# MAGI_sBatteryPowerMega.net
KiCad netlist of a schematic drawn in Altium Designer
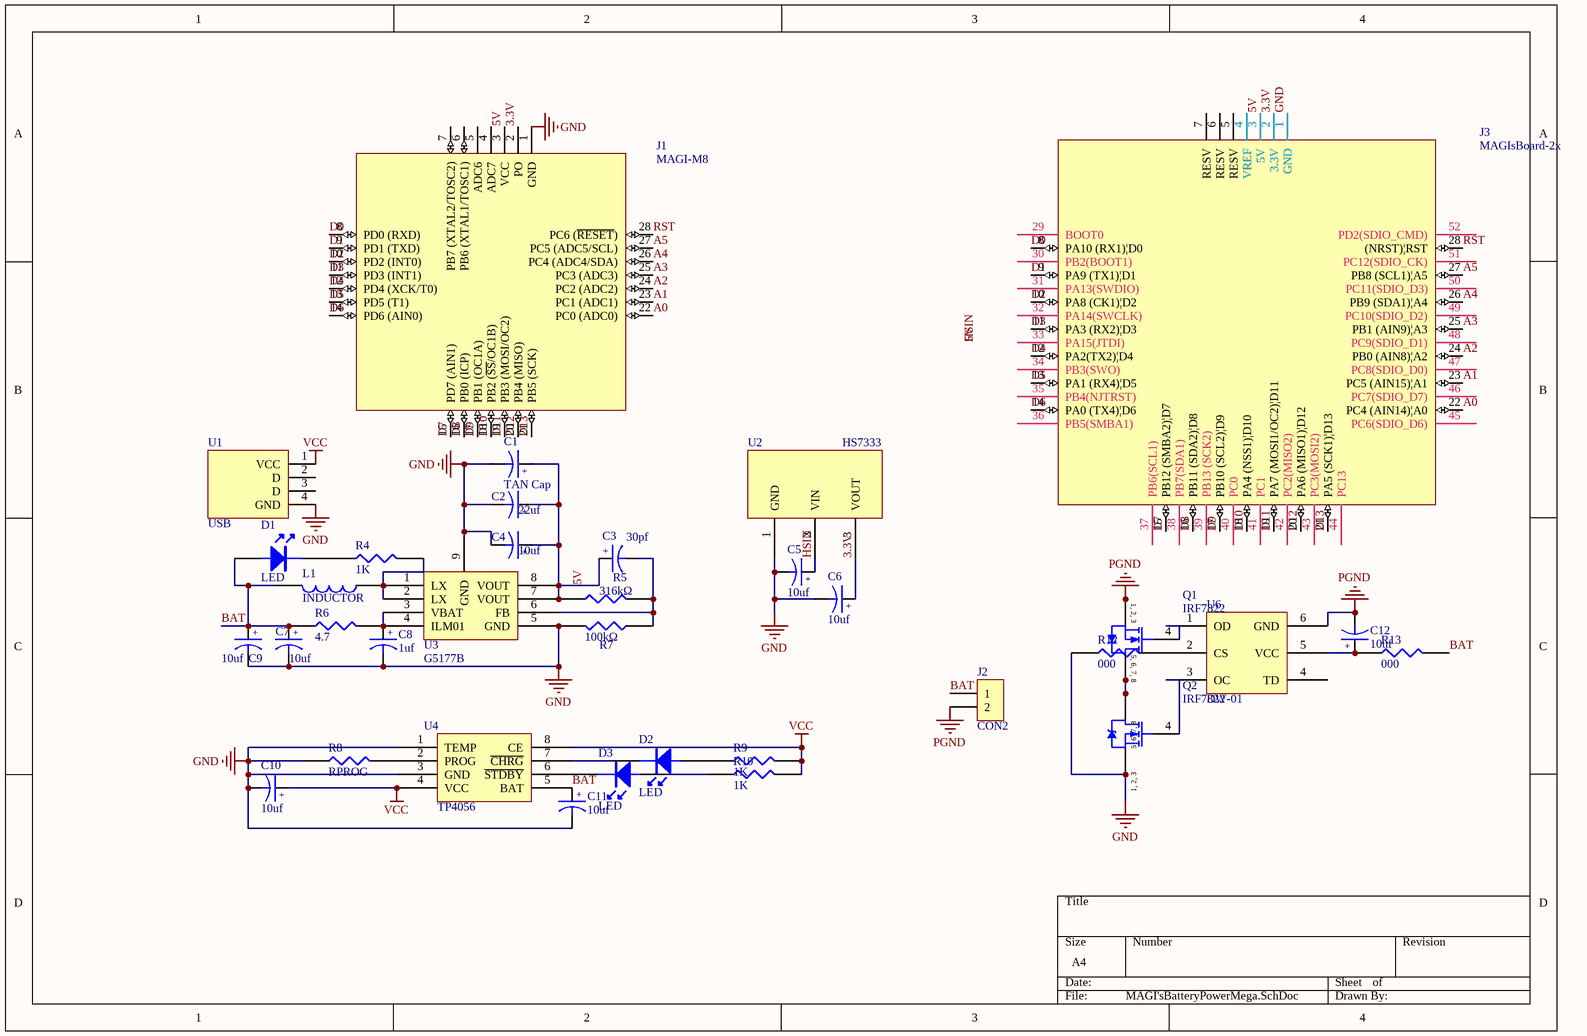
[diagram p0: MAGI'sBatteryPowerMega.SchDoc]

(export (version "E")
  (design (tool "Eeschema 10.0.6"))
  (components
    (comp (ref "C1")
      (value "TAN Cap")
      (footprint "TAN-D-7343")
      (description "Capacitor")
      (libsource (lib "电容器") (part "CAPACITOR POL"))
    )
    (comp (ref "C2")
      (value "22uf")
      (footprint "14-1210")
      (description "Capacitor")
      (libsource (lib "电容器") (part "CAPACITOR POL"))
    )
    (comp (ref "C3")
      (value "30pf")
      (footprint "6-0805_N")
      (description "Capacitor")
      (libsource (lib "电容器") (part "CAPACITOR POL"))
    )
    (comp (ref "C4")
      (value "10uf")
      (footprint "6-0805_N")
      (description "Capacitor")
      (libsource (lib "电容器") (part "CAPACITOR POL"))
    )
    (comp (ref "C5")
      (value "10uf")
      (footprint "6-0805_N")
      (description "Capacitor")
      (libsource (lib "电容器") (part "CAPACITOR POL"))
    )
    (comp (ref "C6")
      (value "10uf")
      (footprint "6-0805_N")
      (description "Capacitor")
      (libsource (lib "电容器") (part "CAPACITOR POL"))
    )
    (comp (ref "C7")
      (value "10uf")
      (footprint "6-0805_N")
      (description "Capacitor")
      (libsource (lib "电容器") (part "CAPACITOR POL"))
    )
    (comp (ref "C8")
      (value "1uf")
      (footprint "6-0805_N")
      (description "Capacitor")
      (libsource (lib "电容器") (part "CAPACITOR POL"))
    )
    (comp (ref "C9")
      (value "10uf")
      (footprint "6-0805_N")
      (description "Capacitor")
      (libsource (lib "电容器") (part "CAPACITOR POL"))
    )
    (comp (ref "C10")
      (value "10uf")
      (footprint "6-0805_N")
      (description "Capacitor")
      (libsource (lib "电容器") (part "CAPACITOR POL"))
    )
    (comp (ref "C11")
      (value "10uf")
      (footprint "6-0805_N")
      (description "Capacitor")
      (libsource (lib "电容器") (part "CAPACITOR POL"))
    )
    (comp (ref "C12")
      (value "10uf")
      (footprint "6-0805_N")
      (description "Capacitor")
      (libsource (lib "电容器") (part "CAPACITOR POL"))
    )
    (comp (ref "D1") (value "LED") (footprint "6-0805_N") (libsource (lib "二极管") (part "LED")))
    (comp (ref "D2") (value "LED") (footprint "6-0805_N") (libsource (lib "二极管") (part "LED")))
    (comp (ref "D3") (value "LED") (footprint "6-0805_N") (libsource (lib "二极管") (part "LED")))
    (comp (ref "J1") (value "MAGI-M8") (footprint "MAGI-M8") (libsource (lib "MAGI-M8") (part "MAGI-M8")))
    (comp (ref "J2")
      (value "CON2")
      (footprint "18650")
      (description "Connector")
      (libsource (lib "CON系列") (part "CON2"))
    )
    (comp (ref "J3")
      (value "MAGIsBoard-2x")
      (footprint "MAGIsBoard-2x")
      (libsource (lib "MAGIsBoard") (part "MAGIsBoard-2x"))
    )
    (comp (ref "L1") (value "INDUCTOR") (footprint "7*7") (libsource (lib "汇总") (part "INDUCTOR")))
    (comp (ref "Q1")
      (value "IRF7822")
      (footprint "SO-8_N")
      (description "HEXFET Power MOSFET")
      (fields (field (name "PUBLISHER") "Altium Limited"))
      (libsource (lib "IR Discrete MOSFET - Power") (part "IRF7822"))
    )
    (comp (ref "Q2")
      (value "IRF7822")
      (footprint "SO-8_N")
      (description "HEXFET Power MOSFET")
      (fields (field (name "PUBLISHER") "Altium Limited"))
      (libsource (lib "IR Discrete MOSFET - Power") (part "IRF7822"))
    )
    (comp (ref "R4") (value "1K") (footprint "6-0805_N") (libsource (lib "电阻器") (part "RES1")))
    (comp (ref "R5") (value "316kΩ") (footprint "6-0805_N") (libsource (lib "电阻器") (part "RES1")))
    (comp (ref "R6") (value "4.7") (footprint "6-0805_N") (libsource (lib "电阻器") (part "RES1")))
    (comp (ref "R7") (value "100kΩ") (footprint "6-0805_N") (libsource (lib "电阻器") (part "RES1")))
    (comp (ref "R8") (value "RPROG") (footprint "6-0805_N") (libsource (lib "电阻器") (part "RES1")))
    (comp (ref "R9") (value "1K") (footprint "6-0805_N") (libsource (lib "电阻器") (part "RES1")))
    (comp (ref "R10") (value "1K") (footprint "6-0805_N") (libsource (lib "电阻器") (part "RES1")))
    (comp (ref "R12") (value "000") (footprint "6-0805_n") (libsource (lib "电阻器") (part "RES1")))
    (comp (ref "R13") (value "000") (footprint "6-0805_n") (libsource (lib "电阻器") (part "RES1")))
    (comp (ref "U1") (value "USB") (footprint "MicroUSB") (libsource (lib "USB接口") (part "USB")))
    (comp (ref "U2") (value "HS7333") (footprint "HS7333") (libsource (lib "PMIC") (part "HS7333")))
    (comp (ref "U3") (value "G5177B") (footprint "G5177B") (libsource (lib "PMIC") (part "G5177B")))
    (comp (ref "U4") (value "TP4056") (footprint "TP4056") (libsource (lib "PMIC") (part "TP4056")))
    (comp (ref "U6") (value "DW-01") (footprint "TPS2513") (libsource (lib "PMIC") (part "TPS2513")))
  )
  (nets
    (net (code "1") (name "/3.3V") (class "Default")
      (node (ref "C6") (pin "1") (pinfunction "1_1") (pintype "passive"))
      (node (ref "J1") (pin "2") (pinfunction "PO_2") (pintype "power_in"))
      (node (ref "J3") (pin "2") (pinfunction "3.3V_2") (pintype "power_in"))
      (node (ref "U2") (pin "3") (pinfunction "VOUT_3") (pintype "passive"))
    )
    (net (code "2") (name "/5V") (class "Default")
      (node (ref "C1") (pin "1") (pinfunction "1_1") (pintype "passive"))
      (node (ref "C2") (pin "1") (pinfunction "1_1") (pintype "passive"))
      (node (ref "C3") (pin "1") (pinfunction "1_1") (pintype "passive"))
      (node (ref "C4") (pin "1") (pinfunction "1_1") (pintype "passive"))
      (node (ref "C5") (pin "1") (pinfunction "1_1") (pintype "passive"))
      (node (ref "J1") (pin "3") (pinfunction "VCC_3") (pintype "power_in"))
      (node (ref "J3") (pin "3") (pinfunction "5V_3") (pintype "power_in"))
      (node (ref "R5") (pin "1") (pinfunction "1_1") (pintype "passive"))
      (node (ref "U2") (pin "2") (pinfunction "VIN_2") (pintype "passive"))
      (node (ref "U3") (pin "7") (pinfunction "VOUT_7") (pintype "passive"))
      (node (ref "U3") (pin "8") (pinfunction "VOUT_8") (pintype "passive"))
    )
    (net (code "3") (name "/A0") (class "Default")
      (node (ref "J1") (pin "22") (pinfunction "PC0_(ADC0)_22") (pintype "bidirectional"))
      (node (ref "J3") (pin "22") (pinfunction "PC4_(AIN14)¦A0_22") (pintype "bidirectional"))
    )
    (net (code "4") (name "/A1") (class "Default")
      (node (ref "J1") (pin "23") (pinfunction "PC1_(ADC1)_23") (pintype "bidirectional"))
      (node (ref "J3") (pin "23") (pinfunction "PC5_(AIN15)¦A1_23") (pintype "bidirectional"))
    )
    (net (code "5") (name "/A2") (class "Default")
      (node (ref "J1") (pin "24") (pinfunction "PC2_(ADC2)_24") (pintype "bidirectional"))
      (node (ref "J3") (pin "24") (pinfunction "PB0_(AIN8)¦A2_24") (pintype "bidirectional"))
    )
    (net (code "6") (name "/A3") (class "Default")
      (node (ref "J1") (pin "25") (pinfunction "PC3_(ADC3)_25") (pintype "bidirectional"))
      (node (ref "J3") (pin "25") (pinfunction "PB1_(AIN9)¦A3_25") (pintype "bidirectional"))
    )
    (net (code "7") (name "/A4") (class "Default")
      (node (ref "J1") (pin "26") (pinfunction "PC4_(ADC4/SDA)_26") (pintype "bidirectional"))
      (node (ref "J3") (pin "26") (pinfunction "PB9_(SDA1)¦A4_26") (pintype "bidirectional"))
    )
    (net (code "8") (name "/A5") (class "Default")
      (node (ref "J1") (pin "27") (pinfunction "PC5_(ADC5/SCL)_27") (pintype "bidirectional"))
      (node (ref "J3") (pin "27") (pinfunction "PB8_(SCL1)¦A5_27") (pintype "bidirectional"))
    )
    (net (code "9") (name "/BAT") (class "Default")
      (node (ref "C11") (pin "1") (pinfunction "1_1") (pintype "passive"))
      (node (ref "C7") (pin "1") (pinfunction "1_1") (pintype "passive"))
      (node (ref "C9") (pin "1") (pinfunction "1_1") (pintype "passive"))
      (node (ref "D1") (pin "1") (pinfunction "1_1") (pintype "passive"))
      (node (ref "J2") (pin "1") (pinfunction "1_1") (pintype "passive"))
      (node (ref "L1") (pin "2") (pinfunction "2_2") (pintype "passive"))
      (node (ref "R13") (pin "2") (pinfunction "2_2") (pintype "passive"))
      (node (ref "R6") (pin "1") (pinfunction "1_1") (pintype "passive"))
      (node (ref "U4") (pin "5") (pinfunction "BAT_5") (pintype "passive"))
    )
    (net (code "10") (name "/D0") (class "Default")
      (node (ref "J1") (pin "8") (pinfunction "PD0_(RXD)_8") (pintype "bidirectional"))
      (node (ref "J3") (pin "8") (pinfunction "PA10_(RX1)¦D0_8") (pintype "bidirectional"))
    )
    (net (code "11") (name "/D1") (class "Default")
      (node (ref "J1") (pin "9") (pinfunction "PD1_(TXD)_9") (pintype "bidirectional"))
      (node (ref "J3") (pin "9") (pinfunction "PA9_(TX1)¦D1_9") (pintype "bidirectional"))
    )
    (net (code "12") (name "/D2") (class "Default")
      (node (ref "J1") (pin "10") (pinfunction "PD2_(INT0)_10") (pintype "bidirectional"))
      (node (ref "J3") (pin "10") (pinfunction "PA8_(CK1)¦D2_10") (pintype "bidirectional"))
    )
    (net (code "13") (name "/D3") (class "Default")
      (node (ref "J1") (pin "11") (pinfunction "PD3_(INT1)_11") (pintype "bidirectional"))
      (node (ref "J3") (pin "11") (pinfunction "PA3_(RX2)¦D3_11") (pintype "bidirectional"))
    )
    (net (code "14") (name "/D4") (class "Default")
      (node (ref "J1") (pin "12") (pinfunction "PD4_(XCK/T0)_12") (pintype "bidirectional"))
      (node (ref "J3") (pin "12") (pinfunction "PA2(TX2)¦D4_12") (pintype "bidirectional"))
    )
    (net (code "15") (name "/D5") (class "Default")
      (node (ref "J1") (pin "13") (pinfunction "PD5_(T1)_13") (pintype "bidirectional"))
      (node (ref "J3") (pin "13") (pinfunction "PA1_(RX4)¦D5_13") (pintype "bidirectional"))
    )
    (net (code "16") (name "/D6") (class "Default")
      (node (ref "J1") (pin "14") (pinfunction "PD6_(AIN0)_14") (pintype "bidirectional"))
      (node (ref "J3") (pin "14") (pinfunction "PA0_(TX4)¦D6_14") (pintype "bidirectional"))
    )
    (net (code "17") (name "/D7") (class "Default")
      (node (ref "J1") (pin "15") (pinfunction "PD7_(AIN1)_15") (pintype "bidirectional"))
      (node (ref "J3") (pin "15") (pinfunction "PB12_(SMBA2)¦D7_15") (pintype "bidirectional"))
    )
    (net (code "18") (name "/D8") (class "Default")
      (node (ref "J1") (pin "16") (pinfunction "PB0_(ICP)_16") (pintype "bidirectional"))
      (node (ref "J3") (pin "16") (pinfunction "PB11_(SDA2)¦D8_16") (pintype "bidirectional"))
    )
    (net (code "19") (name "/D9") (class "Default")
      (node (ref "J1") (pin "17") (pinfunction "PB1_(OC1A)_17") (pintype "bidirectional"))
      (node (ref "J3") (pin "17") (pinfunction "PB10_(SCL2)¦D9_17") (pintype "bidirectional"))
    )
    (net (code "20") (name "/D10") (class "Default")
      (node (ref "J1") (pin "18") (pinfunction "PB2_(~{SS}/OC1B)_18") (pintype "bidirectional"))
      (node (ref "J3") (pin "18") (pinfunction "PA4_(NSS1)¦D10_18") (pintype "bidirectional"))
    )
    (net (code "21") (name "/D11") (class "Default")
      (node (ref "J1") (pin "19") (pinfunction "PB3_(MOSI/OC2)_19") (pintype "bidirectional"))
      (node (ref "J3") (pin "19") (pinfunction "PA7_(MOSI1/OC2)¦D11_19") (pintype "bidirectional"))
    )
    (net (code "22") (name "/D12") (class "Default")
      (node (ref "J1") (pin "20") (pinfunction "PB4_(MISO)_20") (pintype "bidirectional"))
      (node (ref "J3") (pin "20") (pinfunction "PA6_(MISO1)¦D12_20") (pintype "bidirectional"))
    )
    (net (code "23") (name "/D13") (class "Default")
      (node (ref "J1") (pin "21") (pinfunction "PB5_(SCK)_21") (pintype "bidirectional"))
      (node (ref "J3") (pin "21") (pinfunction "PA5_(SCK1)¦D13_21") (pintype "bidirectional"))
    )
    (net (code "24") (name "/RST") (class "Default")
      (node (ref "J1") (pin "28") (pinfunction "PC6_(~{RESET})_28") (pintype "bidirectional"))
      (node (ref "J3") (pin "28") (pinfunction "(NRST)¦RST_28") (pintype "bidirectional"))
    )
    (net (code "25") (name "GND") (class "Default")
      (node (ref "C1") (pin "2") (pinfunction "2_2") (pintype "passive"))
      (node (ref "C10") (pin "2") (pinfunction "2_2") (pintype "passive"))
      (node (ref "C11") (pin "2") (pinfunction "2_2") (pintype "passive"))
      (node (ref "C2") (pin "2") (pinfunction "2_2") (pintype "passive"))
      (node (ref "C4") (pin "2") (pinfunction "2_2") (pintype "passive"))
      (node (ref "C5") (pin "2") (pinfunction "2_2") (pintype "passive"))
      (node (ref "C6") (pin "2") (pinfunction "2_2") (pintype "passive"))
      (node (ref "C7") (pin "2") (pinfunction "2_2") (pintype "passive"))
      (node (ref "C8") (pin "2") (pinfunction "2_2") (pintype "passive"))
      (node (ref "C9") (pin "2") (pinfunction "2_2") (pintype "passive"))
      (node (ref "J1") (pin "1") (pinfunction "GND_1") (pintype "power_in"))
      (node (ref "J3") (pin "1") (pinfunction "GND_1") (pintype "power_in"))
      (node (ref "Q2") (pin "1") (pinfunction "S_1") (pintype "passive"))
      (node (ref "Q2") (pin "2") (pinfunction "S_2") (pintype "passive"))
      (node (ref "Q2") (pin "3") (pinfunction "S_3") (pintype "passive"))
      (node (ref "R12") (pin "1") (pinfunction "1_1") (pintype "passive"))
      (node (ref "R7") (pin "2") (pinfunction "2_2") (pintype "passive"))
      (node (ref "R8") (pin "1") (pinfunction "1_1") (pintype "passive"))
      (node (ref "U1") (pin "4") (pinfunction "GND_4") (pintype "passive"))
      (node (ref "U2") (pin "1") (pinfunction "GND_1") (pintype "passive"))
      (node (ref "U3") (pin "5") (pinfunction "GND_5") (pintype "passive"))
      (node (ref "U3") (pin "9") (pinfunction "GND_9") (pintype "passive"))
      (node (ref "U4") (pin "1") (pinfunction "TEMP_1") (pintype "passive"))
      (node (ref "U4") (pin "3") (pinfunction "GND_3") (pintype "passive"))
    )
    (net (code "26") (name "Net-(D1-Pad2)") (class "Default")
      (node (ref "D1") (pin "2") (pinfunction "2_2") (pintype "passive"))
      (node (ref "R4") (pin "1") (pinfunction "1_1") (pintype "passive"))
    )
    (net (code "27") (name "Net-(D2-Pad1)") (class "Default")
      (node (ref "D2") (pin "1") (pinfunction "1_1") (pintype "passive"))
      (node (ref "R9") (pin "1") (pinfunction "1_1") (pintype "passive"))
    )
    (net (code "28") (name "Net-(D3-Pad1)") (class "Default")
      (node (ref "D3") (pin "1") (pinfunction "1_1") (pintype "passive"))
      (node (ref "R10") (pin "1") (pinfunction "1_1") (pintype "passive"))
    )
    (net (code "29") (name "Net-(L1-Pad1)") (class "Default")
      (node (ref "L1") (pin "1") (pinfunction "1_1") (pintype "passive"))
      (node (ref "R4") (pin "2") (pinfunction "2_2") (pintype "passive"))
      (node (ref "U3") (pin "1") (pinfunction "LX_1") (pintype "passive"))
      (node (ref "U3") (pin "2") (pinfunction "LX_2") (pintype "passive"))
    )
    (net (code "30") (name "Net-(Q1-D-Pad5)") (class "Default")
      (node (ref "Q1") (pin "5") (pinfunction "D_5") (pintype "passive"))
      (node (ref "Q1") (pin "6") (pinfunction "D_6") (pintype "passive"))
      (node (ref "Q1") (pin "7") (pinfunction "D_7") (pintype "passive"))
      (node (ref "Q1") (pin "8") (pinfunction "D_8") (pintype "passive"))
      (node (ref "Q2") (pin "5") (pinfunction "D_5") (pintype "passive"))
      (node (ref "Q2") (pin "6") (pinfunction "D_6") (pintype "passive"))
      (node (ref "Q2") (pin "7") (pinfunction "D_7") (pintype "passive"))
      (node (ref "Q2") (pin "8") (pinfunction "D_8") (pintype "passive"))
    )
    (net (code "31") (name "Net-(Q1-G)") (class "Default")
      (node (ref "Q1") (pin "4") (pinfunction "G_4") (pintype "passive"))
      (node (ref "U6") (pin "1") (pinfunction "OD_1") (pintype "passive"))
    )
    (net (code "32") (name "Net-(Q2-G)") (class "Default")
      (node (ref "Q2") (pin "4") (pinfunction "G_4") (pintype "passive"))
      (node (ref "U6") (pin "3") (pinfunction "OC_3") (pintype "passive"))
    )
    (net (code "33") (name "Net-(U3-FB)") (class "Default")
      (node (ref "C3") (pin "2") (pinfunction "2_2") (pintype "passive"))
      (node (ref "R5") (pin "2") (pinfunction "2_2") (pintype "passive"))
      (node (ref "R7") (pin "1") (pinfunction "1_1") (pintype "passive"))
      (node (ref "U3") (pin "6") (pinfunction "FB_6") (pintype "passive"))
    )
    (net (code "34") (name "Net-(U3-ILM01)") (class "Default")
      (node (ref "C8") (pin "1") (pinfunction "1_1") (pintype "passive"))
      (node (ref "R6") (pin "2") (pinfunction "2_2") (pintype "passive"))
      (node (ref "U3") (pin "3") (pinfunction "VBAT_3") (pintype "passive"))
      (node (ref "U3") (pin "4") (pinfunction "ILM01_4") (pintype "passive"))
    )
    (net (code "35") (name "Net-(U4-PROG)") (class "Default")
      (node (ref "R8") (pin "2") (pinfunction "2_2") (pintype "passive"))
      (node (ref "U4") (pin "2") (pinfunction "PROG_2") (pintype "passive"))
    )
    (net (code "36") (name "Net-(U4-~{CHRG})") (class "Default")
      (node (ref "D2") (pin "2") (pinfunction "2_2") (pintype "passive"))
      (node (ref "U4") (pin "7") (pinfunction "~{CHRG}_7") (pintype "passive"))
    )
    (net (code "37") (name "Net-(U4-~{STDBY})") (class "Default")
      (node (ref "D3") (pin "2") (pinfunction "2_2") (pintype "passive"))
      (node (ref "U4") (pin "6") (pinfunction "~{STDBY}_6") (pintype "passive"))
    )
    (net (code "38") (name "Net-(U6-CS)") (class "Default")
      (node (ref "R12") (pin "2") (pinfunction "2_2") (pintype "passive"))
      (node (ref "U6") (pin "2") (pinfunction "CS_2") (pintype "passive"))
    )
    (net (code "39") (name "Net-(U6-VCC)") (class "Default")
      (node (ref "C12") (pin "1") (pinfunction "1_1") (pintype "passive"))
      (node (ref "R13") (pin "1") (pinfunction "1_1") (pintype "passive"))
      (node (ref "U6") (pin "5") (pinfunction "VCC_5") (pintype "passive"))
    )
    (net (code "40") (name "PGND") (class "Default")
      (node (ref "C12") (pin "2") (pinfunction "2_2") (pintype "passive"))
      (node (ref "J2") (pin "2") (pinfunction "2_2") (pintype "passive"))
      (node (ref "Q1") (pin "1") (pinfunction "S_1") (pintype "passive"))
      (node (ref "Q1") (pin "2") (pinfunction "S_2") (pintype "passive"))
      (node (ref "Q1") (pin "3") (pinfunction "S_3") (pintype "passive"))
      (node (ref "U6") (pin "6") (pinfunction "GND_6") (pintype "passive"))
    )
    (net (code "41") (name "VCC") (class "Default")
      (node (ref "C10") (pin "1") (pinfunction "1_1") (pintype "passive"))
      (node (ref "R10") (pin "2") (pinfunction "2_2") (pintype "passive"))
      (node (ref "R9") (pin "2") (pinfunction "2_2") (pintype "passive"))
      (node (ref "U1") (pin "1") (pinfunction "VCC_1") (pintype "passive"))
      (node (ref "U4") (pin "4") (pinfunction "VCC_4") (pintype "passive"))
      (node (ref "U4") (pin "8") (pinfunction "CE_8") (pintype "passive"))
    )
    (net (code "42") (name "unconnected-(J1-ADC6-Pad5)") (class "Default")
      (node (ref "J1") (pin "5") (pinfunction "ADC6_5") (pintype "passive"))
    )
    (net (code "43") (name "unconnected-(J1-ADC7-Pad4)") (class "Default")
      (node (ref "J1") (pin "4") (pinfunction "ADC7_4") (pintype "passive"))
    )
    (net (code "44") (name "unconnected-(J1-PB6_(XTAL1{slash}TOSC1)-Pad6)") (class "Default")
      (node (ref "J1") (pin "6") (pinfunction "PB6_(XTAL1/TOSC1)_6") (pintype "bidirectional"))
    )
    (net (code "45") (name "unconnected-(J1-PB7_(XTAL2{slash}TOSC2)-Pad7)") (class "Default")
      (node (ref "J1") (pin "7") (pinfunction "PB7_(XTAL2/TOSC2)_7") (pintype "bidirectional"))
    )
    (net (code "46") (name "unconnected-(J3-BOOT0-Pad29)") (class "Default")
      (node (ref "J3") (pin "29") (pinfunction "BOOT0_29") (pintype "passive"))
    )
    (net (code "47") (name "unconnected-(J3-PA13(SWDIO)-Pad31)") (class "Default")
      (node (ref "J3") (pin "31") (pinfunction "PA13(SWDIO)_31") (pintype "passive"))
    )
    (net (code "48") (name "unconnected-(J3-PA14(SWCLK)-Pad32)") (class "Default")
      (node (ref "J3") (pin "32") (pinfunction "PA14(SWCLK)_32") (pintype "passive"))
    )
    (net (code "49") (name "unconnected-(J3-PA15(JTDI)-Pad33)") (class "Default")
      (node (ref "J3") (pin "33") (pinfunction "PA15(JTDI)_33") (pintype "passive"))
    )
    (net (code "50") (name "unconnected-(J3-PB2(BOOT1)-Pad30)") (class "Default")
      (node (ref "J3") (pin "30") (pinfunction "PB2(BOOT1)_30") (pintype "passive"))
    )
    (net (code "51") (name "unconnected-(J3-PB3(SWO)-Pad34)") (class "Default")
      (node (ref "J3") (pin "34") (pinfunction "PB3(SWO)_34") (pintype "passive"))
    )
    (net (code "52") (name "unconnected-(J3-PB4(NJTRST)-Pad35)") (class "Default")
      (node (ref "J3") (pin "35") (pinfunction "PB4(NJTRST)_35") (pintype "passive"))
    )
    (net (code "53") (name "unconnected-(J3-PB5(SMBA1)-Pad36)") (class "Default")
      (node (ref "J3") (pin "36") (pinfunction "PB5(SMBA1)_36") (pintype "passive"))
    )
    (net (code "54") (name "unconnected-(J3-PB6(SCL1)-Pad37)") (class "Default")
      (node (ref "J3") (pin "37") (pinfunction "PB6(SCL1)_37") (pintype "passive"))
    )
    (net (code "55") (name "unconnected-(J3-PB7(SDA1)-Pad38)") (class "Default")
      (node (ref "J3") (pin "38") (pinfunction "PB7(SDA1)_38") (pintype "passive"))
    )
    (net (code "56") (name "unconnected-(J3-PB13_(SCK2)-Pad39)") (class "Default")
      (node (ref "J3") (pin "39") (pinfunction "PB13_(SCK2)_39") (pintype "passive"))
    )
    (net (code "57") (name "unconnected-(J3-PC0-Pad40)") (class "Default")
      (node (ref "J3") (pin "40") (pinfunction "PC0_40") (pintype "passive"))
    )
    (net (code "58") (name "unconnected-(J3-PC1-Pad41)") (class "Default")
      (node (ref "J3") (pin "41") (pinfunction "PC1_41") (pintype "passive"))
    )
    (net (code "59") (name "unconnected-(J3-PC2(MISO2)-Pad42)") (class "Default")
      (node (ref "J3") (pin "42") (pinfunction "PC2(MISO2)_42") (pintype "passive"))
    )
    (net (code "60") (name "unconnected-(J3-PC3(MOSI2)-Pad43)") (class "Default")
      (node (ref "J3") (pin "43") (pinfunction "PC3(MOSI2)_43") (pintype "passive"))
    )
    (net (code "61") (name "unconnected-(J3-PC6(SDIO_D6)-Pad45)") (class "Default")
      (node (ref "J3") (pin "45") (pinfunction "PC6(SDIO_D6)_45") (pintype "passive"))
    )
    (net (code "62") (name "unconnected-(J3-PC7(SDIO_D7)-Pad46)") (class "Default")
      (node (ref "J3") (pin "46") (pinfunction "PC7(SDIO_D7)_46") (pintype "passive"))
    )
    (net (code "63") (name "unconnected-(J3-PC8(SDIO_D0)-Pad47)") (class "Default")
      (node (ref "J3") (pin "47") (pinfunction "PC8(SDIO_D0)_47") (pintype "passive"))
    )
    (net (code "64") (name "unconnected-(J3-PC9(SDIO_D1)-Pad48)") (class "Default")
      (node (ref "J3") (pin "48") (pinfunction "PC9(SDIO_D1)_48") (pintype "passive"))
    )
    (net (code "65") (name "unconnected-(J3-PC10(SDIO_D2)-Pad49)") (class "Default")
      (node (ref "J3") (pin "49") (pinfunction "PC10(SDIO_D2)_49") (pintype "passive"))
    )
    (net (code "66") (name "unconnected-(J3-PC11(SDIO_D3)-Pad50)") (class "Default")
      (node (ref "J3") (pin "50") (pinfunction "PC11(SDIO_D3)_50") (pintype "passive"))
    )
    (net (code "67") (name "unconnected-(J3-PC12(SDIO_CK)-Pad51)") (class "Default")
      (node (ref "J3") (pin "51") (pinfunction "PC12(SDIO_CK)_51") (pintype "passive"))
    )
    (net (code "68") (name "unconnected-(J3-PC13-Pad44)") (class "Default")
      (node (ref "J3") (pin "44") (pinfunction "PC13_44") (pintype "passive"))
    )
    (net (code "69") (name "unconnected-(J3-PD2(SDIO_CMD)-Pad52)") (class "Default")
      (node (ref "J3") (pin "52") (pinfunction "PD2(SDIO_CMD)_52") (pintype "passive"))
    )
    (net (code "70") (name "unconnected-(J3-RESV-Pad5)") (class "Default")
      (node (ref "J3") (pin "5") (pinfunction "RESV_5") (pintype "passive"))
    )
    (net (code "71") (name "unconnected-(J3-RESV-Pad6)") (class "Default")
      (node (ref "J3") (pin "6") (pinfunction "RESV_6") (pintype "passive"))
    )
    (net (code "72") (name "unconnected-(J3-RESV-Pad7)") (class "Default")
      (node (ref "J3") (pin "7") (pinfunction "RESV_7") (pintype "passive"))
    )
    (net (code "73") (name "unconnected-(J3-VREF-Pad4)") (class "Default")
      (node (ref "J3") (pin "4") (pinfunction "VREF_4") (pintype "passive"))
    )
    (net (code "74") (name "unconnected-(U1-D-Pad2)") (class "Default")
      (node (ref "U1") (pin "2") (pinfunction "D_2") (pintype "passive"))
    )
    (net (code "75") (name "unconnected-(U1-D-Pad3)") (class "Default")
      (node (ref "U1") (pin "3") (pinfunction "D_3") (pintype "passive"))
    )
    (net (code "76") (name "unconnected-(U6-TD-Pad4)") (class "Default")
      (node (ref "U6") (pin "4") (pinfunction "TD_4") (pintype "passive"))
    )
  )
)
